# PWR.net
KiCad netlist of a schematic drawn in Altium Designer
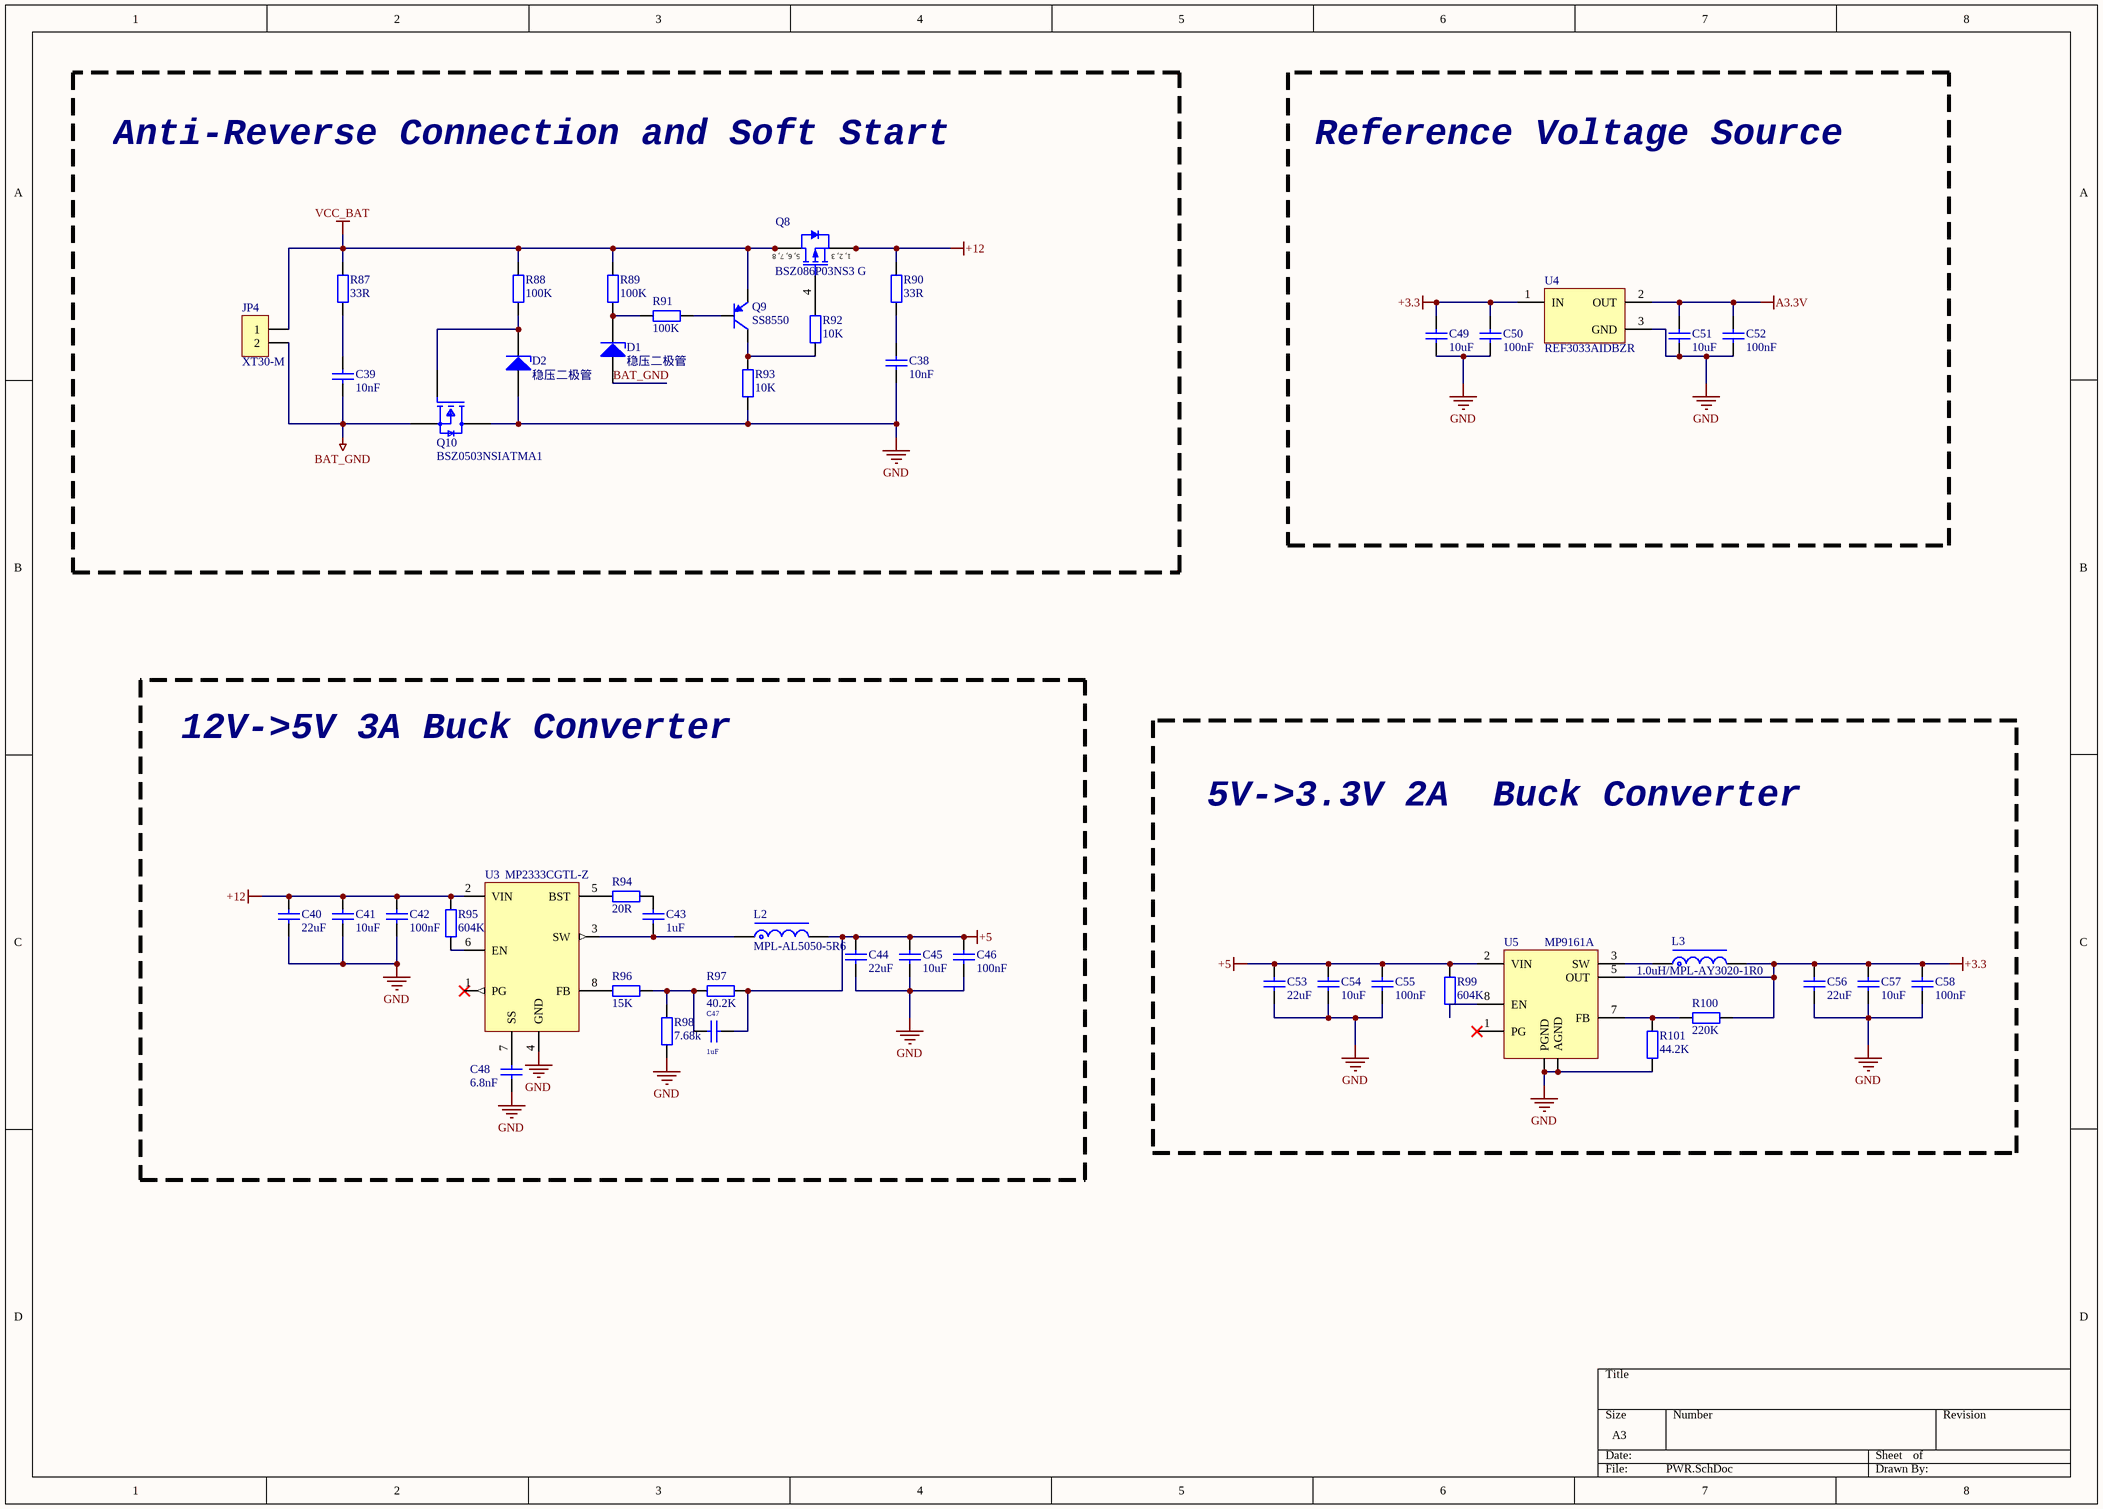
[diagram p0: PWR.SchDoc]

(export (version "E")
  (design (tool "Eeschema 10.0.6"))
  (components
    (comp (ref "C38")
      (value "10nF")
      (footprint "C0402_M")
      (description "贴片电容/MLCC电容")
      (libsource (lib "0.1 - 电阻-电容-电感-保险丝-晶振-晶体-磁珠-电位器-法拉电容-馈通电容") (part "C"))
    )
    (comp (ref "C39")
      (value "10nF")
      (footprint "C0402_M")
      (description "贴片电容/MLCC电容")
      (libsource (lib "0.1 - 电阻-电容-电感-保险丝-晶振-晶体-磁珠-电位器-法拉电容-馈通电容") (part "C"))
    )
    (comp (ref "C40")
      (value "22uF")
      (footprint "C0402_M")
      (description "贴片电容/MLCC电容")
      (libsource (lib "0.1 - 电阻-电容-电感-保险丝-晶振-晶体-磁珠-电位器-法拉电容-馈通电容") (part "C"))
    )
    (comp (ref "C41")
      (value "10uF")
      (footprint "C0402_M")
      (description "贴片电容/MLCC电容")
      (libsource (lib "0.1 - 电阻-电容-电感-保险丝-晶振-晶体-磁珠-电位器-法拉电容-馈通电容") (part "C"))
    )
    (comp (ref "C42")
      (value "100nF")
      (footprint "C0402_M")
      (description "贴片电容/MLCC电容")
      (libsource (lib "0.1 - 电阻-电容-电感-保险丝-晶振-晶体-磁珠-电位器-法拉电容-馈通电容") (part "C"))
    )
    (comp (ref "C43")
      (value "1uF")
      (footprint "C0402_M")
      (description "贴片电容/MLCC电容")
      (libsource (lib "0.1 - 电阻-电容-电感-保险丝-晶振-晶体-磁珠-电位器-法拉电容-馈通电容") (part "C"))
    )
    (comp (ref "C44")
      (value "22uF")
      (footprint "C0402_M")
      (description "贴片电容/MLCC电容")
      (libsource (lib "0.1 - 电阻-电容-电感-保险丝-晶振-晶体-磁珠-电位器-法拉电容-馈通电容") (part "C"))
    )
    (comp (ref "C45")
      (value "10uF")
      (footprint "C0402_M")
      (description "贴片电容/MLCC电容")
      (libsource (lib "0.1 - 电阻-电容-电感-保险丝-晶振-晶体-磁珠-电位器-法拉电容-馈通电容") (part "C"))
    )
    (comp (ref "C46")
      (value "100nF")
      (footprint "C0402_M")
      (description "贴片电容/MLCC电容")
      (libsource (lib "0.1 - 电阻-电容-电感-保险丝-晶振-晶体-磁珠-电位器-法拉电容-馈通电容") (part "C"))
    )
    (comp (ref "C47")
      (value "1uF")
      (footprint "C0402_M")
      (description "贴片电容/MLCC电容")
      (libsource (lib "0.1 - 电阻-电容-电感-保险丝-晶振-晶体-磁珠-电位器-法拉电容-馈通电容") (part "C"))
    )
    (comp (ref "C48")
      (value "6.8nF")
      (footprint "C0402_M")
      (description "贴片电容/MLCC电容")
      (libsource (lib "0.1 - 电阻-电容-电感-保险丝-晶振-晶体-磁珠-电位器-法拉电容-馈通电容") (part "C"))
    )
    (comp (ref "C49")
      (value "10uF")
      (footprint "C0402_M")
      (description "贴片电容/MLCC电容")
      (libsource (lib "0.1 - 电阻-电容-电感-保险丝-晶振-晶体-磁珠-电位器-法拉电容-馈通电容") (part "C"))
    )
    (comp (ref "C50")
      (value "100nF")
      (footprint "C0402_M")
      (description "贴片电容/MLCC电容")
      (libsource (lib "0.1 - 电阻-电容-电感-保险丝-晶振-晶体-磁珠-电位器-法拉电容-馈通电容") (part "C"))
    )
    (comp (ref "C51")
      (value "10uF")
      (footprint "C0402_M")
      (description "贴片电容/MLCC电容")
      (libsource (lib "0.1 - 电阻-电容-电感-保险丝-晶振-晶体-磁珠-电位器-法拉电容-馈通电容") (part "C"))
    )
    (comp (ref "C52")
      (value "100nF")
      (footprint "C0402_M")
      (description "贴片电容/MLCC电容")
      (libsource (lib "0.1 - 电阻-电容-电感-保险丝-晶振-晶体-磁珠-电位器-法拉电容-馈通电容") (part "C"))
    )
    (comp (ref "C53")
      (value "22uF")
      (footprint "C0402_M")
      (description "贴片电容/MLCC电容")
      (libsource (lib "0.1 - 电阻-电容-电感-保险丝-晶振-晶体-磁珠-电位器-法拉电容-馈通电容") (part "C"))
    )
    (comp (ref "C54")
      (value "10uF")
      (footprint "C0402_M")
      (description "贴片电容/MLCC电容")
      (libsource (lib "0.1 - 电阻-电容-电感-保险丝-晶振-晶体-磁珠-电位器-法拉电容-馈通电容") (part "C"))
    )
    (comp (ref "C55")
      (value "100nF")
      (footprint "C0402_M")
      (description "贴片电容/MLCC电容")
      (libsource (lib "0.1 - 电阻-电容-电感-保险丝-晶振-晶体-磁珠-电位器-法拉电容-馈通电容") (part "C"))
    )
    (comp (ref "C56")
      (value "22uF")
      (footprint "C0402_M")
      (description "贴片电容/MLCC电容")
      (libsource (lib "0.1 - 电阻-电容-电感-保险丝-晶振-晶体-磁珠-电位器-法拉电容-馈通电容") (part "C"))
    )
    (comp (ref "C57")
      (value "10uF")
      (footprint "C0402_M")
      (description "贴片电容/MLCC电容")
      (libsource (lib "0.1 - 电阻-电容-电感-保险丝-晶振-晶体-磁珠-电位器-法拉电容-馈通电容") (part "C"))
    )
    (comp (ref "C58")
      (value "100nF")
      (footprint "C0402_M")
      (description "贴片电容/MLCC电容")
      (libsource (lib "0.1 - 电阻-电容-电感-保险丝-晶振-晶体-磁珠-电位器-法拉电容-馈通电容") (part "C"))
    )
    (comp (ref "D1")
      (value "稳压二极管")
      (footprint "SOD-523")
      (description "Zener Diode")
      (libsource (lib "0.2 - 二极管-TVS-ESD-整流桥-放电管") (part "稳压二极管"))
    )
    (comp (ref "D2")
      (value "稳压二极管")
      (footprint "SOD-523")
      (description "Zener Diode")
      (libsource (lib "0.2 - 二极管-TVS-ESD-整流桥-放电管") (part "稳压二极管"))
    )
    (comp (ref "JP4")
      (value "XT30-M")
      (footprint "XT30PB-M")
      (description "XT30公头")
      (libsource (lib "0.6 - 电源_音频_USB Type-C_HDMI_XT60_5557_D-SUB_RJ45_SD-TF_SIM插座") (part "XT30-M"))
    )
    (comp (ref "L2")
      (value "MPL-AL5050-5R6")
      (footprint "MPL-AL5050")
      (description "一体成型电感")
      (libsource (lib "0.1 - 电阻-电容-电感-保险丝-晶振-晶体-磁珠-电位器-法拉电容-馈通电容") (part "L-Molding Choke"))
    )
    (comp (ref "L3")
      (value "1.0uH/MPL-AY3020-1R0")
      (footprint "MPL-AY3020")
      (description "一体成型电感")
      (libsource (lib "0.1 - 电阻-电容-电感-保险丝-晶振-晶体-磁珠-电位器-法拉电容-馈通电容") (part "L-Molding Choke"))
    )
    (comp (ref "Q8")
      (value "BSZ086P03NS3 G")
      (footprint "INF-PG-TSDSON-8-1_V")
      (fields (field (name "MANUFACTURER") "Infineon"))
      (libsource (lib "Altium Content Vault") (part "INF-PEMOS-SSSGDDDD-8"))
    )
    (comp (ref "Q9")
      (value "SS8550")
      (footprint "SOT23-3N")
      (description "高频放大-PNP型")
      (libsource (lib "0.4 - 三极管-场效应管-可控硅") (part "8550-SMD"))
    )
    (comp (ref "Q10")
      (value "BSZ0503NSIATMA1")
      (footprint "FP-PG-TSDSON-8-MFG")
      (description "BSZ0503NSI series 30V 40A 3.4 mOhm N-Ch S3O8 OptiMOS 5")
      (libsource (lib "海南大学MECHA战队") (part "3085234d4498bcd04bc7e5400bb7c96"))
    )
    (comp (ref "R87")
      (value "33R")
      (footprint "R0402_L")
      (description "贴片电阻0")
      (libsource (lib "海南大学MECHA战队") (part "R-High Precision"))
    )
    (comp (ref "R88")
      (value "100K")
      (footprint "R0402_L")
      (description "贴片电阻0")
      (libsource (lib "海南大学MECHA战队") (part "R-High Precision"))
    )
    (comp (ref "R89")
      (value "100K")
      (footprint "R0402_L")
      (description "贴片电阻0")
      (libsource (lib "海南大学MECHA战队") (part "R-High Precision"))
    )
    (comp (ref "R90")
      (value "33R")
      (footprint "R0402_L")
      (description "贴片电阻0")
      (libsource (lib "海南大学MECHA战队") (part "R-High Precision"))
    )
    (comp (ref "R91")
      (value "100K")
      (footprint "R0402_L")
      (description "贴片电阻0")
      (libsource (lib "海南大学MECHA战队") (part "R-High Precision"))
    )
    (comp (ref "R92")
      (value "10K")
      (footprint "R0402_L")
      (description "贴片电阻0")
      (libsource (lib "海南大学MECHA战队") (part "R-High Precision"))
    )
    (comp (ref "R93")
      (value "10K")
      (footprint "R0402_L")
      (description "贴片电阻0")
      (libsource (lib "海南大学MECHA战队") (part "R-High Precision"))
    )
    (comp (ref "R94")
      (value "20R")
      (footprint "R0402_L")
      (description "贴片电阻0")
      (libsource (lib "海南大学MECHA战队") (part "R-High Precision"))
    )
    (comp (ref "R95")
      (value "604K")
      (footprint "R0402_L")
      (description "贴片电阻0")
      (libsource (lib "海南大学MECHA战队") (part "R-High Precision"))
    )
    (comp (ref "R96")
      (value "15K")
      (footprint "R0402_L")
      (description "贴片电阻0")
      (libsource (lib "海南大学MECHA战队") (part "R-High Precision"))
    )
    (comp (ref "R97")
      (value "40.2K")
      (footprint "R0402_L")
      (description "贴片电阻0")
      (libsource (lib "海南大学MECHA战队") (part "R-High Precision"))
    )
    (comp (ref "R98")
      (value "7.68k")
      (footprint "R0402_L")
      (description "贴片电阻0")
      (libsource (lib "海南大学MECHA战队") (part "R-High Precision"))
    )
    (comp (ref "R99")
      (value "604K")
      (footprint "R0402_L")
      (description "贴片电阻0")
      (libsource (lib "海南大学MECHA战队") (part "R-High Precision"))
    )
    (comp (ref "R100")
      (value "220K")
      (footprint "R0402_L")
      (description "贴片电阻0")
      (libsource (lib "海南大学MECHA战队") (part "R-High Precision"))
    )
    (comp (ref "R101")
      (value "44.2K")
      (footprint "R0402_L")
      (description "贴片电阻0")
      (libsource (lib "海南大学MECHA战队") (part "R-High Precision"))
    )
    (comp (ref "U3")
      (value "MP2333CGTL-Z")
      (footprint "SOT583_MP2333C_MNP")
      (description "Switching Voltage Regulators 3A, 18V, 650kHz, Force CCM, Synchronous Step-Down C")
      (libsource (lib "海南大学MECHA战队") (part "MP2333CGTL-Z"))
    )
    (comp (ref "U4")
      (value "REF3033AIDBZR")
      (footprint "DBZ0003A_N")
      (fields (field (name "MANUFACTURER") "Texas Instruments"))
      (libsource (lib "Altium Content Vault") (part "TI-REF3033DBZ3"))
    )
    (comp (ref "U5") (value "MP9161A") (footprint "SOT23-8") (libsource (lib "海南大学MECHA战队") (part "MP9161A")))
  )
  (nets
    (net (code "1") (name "+3.3") (class "Default")
      (node (ref "C49") (pin "2") (pinfunction "2_2") (pintype "passive"))
      (node (ref "C50") (pin "2") (pinfunction "2_2") (pintype "passive"))
      (node (ref "C56") (pin "2") (pinfunction "2_2") (pintype "passive"))
      (node (ref "C57") (pin "2") (pinfunction "2_2") (pintype "passive"))
      (node (ref "C58") (pin "2") (pinfunction "2_2") (pintype "passive"))
      (node (ref "L3") (pin "2") (pinfunction "2_2") (pintype "passive"))
      (node (ref "R100") (pin "2") (pinfunction "2_2") (pintype "passive"))
      (node (ref "U4") (pin "1") (pinfunction "IN_1") (pintype "power_in"))
      (node (ref "U5") (pin "5") (pinfunction "OUT_5") (pintype "passive"))
    )
    (net (code "2") (name "+5") (class "Default")
      (node (ref "C44") (pin "2") (pinfunction "2_2") (pintype "passive"))
      (node (ref "C45") (pin "2") (pinfunction "2_2") (pintype "passive"))
      (node (ref "C46") (pin "2") (pinfunction "2_2") (pintype "passive"))
      (node (ref "C47") (pin "1") (pinfunction "1_1") (pintype "passive"))
      (node (ref "C53") (pin "2") (pinfunction "2_2") (pintype "passive"))
      (node (ref "C54") (pin "2") (pinfunction "2_2") (pintype "passive"))
      (node (ref "C55") (pin "2") (pinfunction "2_2") (pintype "passive"))
      (node (ref "L2") (pin "2") (pinfunction "2_2") (pintype "passive"))
      (node (ref "R97") (pin "2") (pinfunction "2_2") (pintype "passive"))
      (node (ref "R99") (pin "2") (pinfunction "2_2") (pintype "passive"))
      (node (ref "U5") (pin "2") (pinfunction "VIN_2") (pintype "passive"))
    )
    (net (code "3") (name "+12") (class "Default")
      (node (ref "C40") (pin "2") (pinfunction "2_2") (pintype "passive"))
      (node (ref "C41") (pin "2") (pinfunction "2_2") (pintype "passive"))
      (node (ref "C42") (pin "2") (pinfunction "2_2") (pintype "passive"))
      (node (ref "Q8") (pin "1") (pinfunction "SOURCE_1") (pintype "passive"))
      (node (ref "Q8") (pin "2") (pinfunction "SOURCE_2") (pintype "passive"))
      (node (ref "Q8") (pin "3") (pinfunction "SOURCE_3") (pintype "passive"))
      (node (ref "R90") (pin "2") (pinfunction "2_2") (pintype "passive"))
      (node (ref "R95") (pin "2") (pinfunction "2_2") (pintype "passive"))
      (node (ref "U3") (pin "2") (pinfunction "VIN_2") (pintype "power_in"))
    )
    (net (code "4") (name "A3.3V") (class "Default")
      (node (ref "C51") (pin "2") (pinfunction "2_2") (pintype "passive"))
      (node (ref "C52") (pin "2") (pinfunction "2_2") (pintype "passive"))
      (node (ref "U4") (pin "2") (pinfunction "OUT_2") (pintype "power_in"))
    )
    (net (code "5") (name "BAT_GND") (class "Default")
      (node (ref "C39") (pin "1") (pinfunction "1_1") (pintype "passive"))
      (node (ref "D1") (pin "1") (pinfunction "A_1") (pintype "passive"))
      (node (ref "JP4") (pin "2") (pinfunction "2_2") (pintype "passive"))
      (node (ref "Q10") (pin "1-2-3") (pinfunction "S_1-2-3") (pintype "passive"))
    )
    (net (code "6") (name "GND") (class "Default")
      (node (ref "C38") (pin "1") (pinfunction "1_1") (pintype "passive"))
      (node (ref "C40") (pin "1") (pinfunction "1_1") (pintype "passive"))
      (node (ref "C41") (pin "1") (pinfunction "1_1") (pintype "passive"))
      (node (ref "C42") (pin "1") (pinfunction "1_1") (pintype "passive"))
      (node (ref "C44") (pin "1") (pinfunction "1_1") (pintype "passive"))
      (node (ref "C45") (pin "1") (pinfunction "1_1") (pintype "passive"))
      (node (ref "C46") (pin "1") (pinfunction "1_1") (pintype "passive"))
      (node (ref "C48") (pin "2") (pinfunction "2_2") (pintype "passive"))
      (node (ref "C49") (pin "1") (pinfunction "1_1") (pintype "passive"))
      (node (ref "C50") (pin "1") (pinfunction "1_1") (pintype "passive"))
      (node (ref "C51") (pin "1") (pinfunction "1_1") (pintype "passive"))
      (node (ref "C52") (pin "1") (pinfunction "1_1") (pintype "passive"))
      (node (ref "C53") (pin "1") (pinfunction "1_1") (pintype "passive"))
      (node (ref "C54") (pin "1") (pinfunction "1_1") (pintype "passive"))
      (node (ref "C55") (pin "1") (pinfunction "1_1") (pintype "passive"))
      (node (ref "C56") (pin "1") (pinfunction "1_1") (pintype "passive"))
      (node (ref "C57") (pin "1") (pinfunction "1_1") (pintype "passive"))
      (node (ref "C58") (pin "1") (pinfunction "1_1") (pintype "passive"))
      (node (ref "D2") (pin "1") (pinfunction "A_1") (pintype "passive"))
      (node (ref "Q10") (pin "5-6-7-8") (pinfunction "D_5-6-7-8") (pintype "passive"))
      (node (ref "R101") (pin "2") (pinfunction "2_2") (pintype "passive"))
      (node (ref "R93") (pin "2") (pinfunction "2_2") (pintype "passive"))
      (node (ref "R98") (pin "2") (pinfunction "2_2") (pintype "passive"))
      (node (ref "U3") (pin "4") (pinfunction "GND_4") (pintype "power_in"))
      (node (ref "U4") (pin "3") (pinfunction "GND_3") (pintype "power_in"))
      (node (ref "U5") (pin "4") (pinfunction "PGND_4") (pintype "passive"))
      (node (ref "U5") (pin "6") (pinfunction "AGND_6") (pintype "passive"))
    )
    (net (code "7") (name "Net-(C38-Pad2)") (class "Default")
      (node (ref "C38") (pin "2") (pinfunction "2_2") (pintype "passive"))
      (node (ref "R90") (pin "1") (pinfunction "1_1") (pintype "passive"))
    )
    (net (code "8") (name "Net-(C39-Pad2)") (class "Default")
      (node (ref "C39") (pin "2") (pinfunction "2_2") (pintype "passive"))
      (node (ref "R87") (pin "1") (pinfunction "1_1") (pintype "passive"))
    )
    (net (code "9") (name "Net-(C43-Pad2)") (class "Default")
      (node (ref "C43") (pin "2") (pinfunction "2_2") (pintype "passive"))
      (node (ref "R94") (pin "1") (pinfunction "1_1") (pintype "passive"))
    )
    (net (code "10") (name "Net-(C47-Pad2)") (class "Default")
      (node (ref "C47") (pin "2") (pinfunction "2_2") (pintype "passive"))
      (node (ref "R96") (pin "1") (pinfunction "1_1") (pintype "passive"))
      (node (ref "R97") (pin "1") (pinfunction "1_1") (pintype "passive"))
      (node (ref "R98") (pin "1") (pinfunction "1_1") (pintype "passive"))
    )
    (net (code "11") (name "Net-(D1-K)") (class "Default")
      (node (ref "D1") (pin "2") (pinfunction "K_2") (pintype "passive"))
      (node (ref "R89") (pin "1") (pinfunction "1_1") (pintype "passive"))
      (node (ref "R91") (pin "2") (pinfunction "2_2") (pintype "passive"))
    )
    (net (code "12") (name "Net-(D2-K)") (class "Default")
      (node (ref "D2") (pin "2") (pinfunction "K_2") (pintype "passive"))
      (node (ref "Q10") (pin "4") (pinfunction "G_4") (pintype "passive"))
      (node (ref "R88") (pin "1") (pinfunction "1_1") (pintype "passive"))
    )
    (net (code "13") (name "Net-(Q8-GATE)") (class "Default")
      (node (ref "Q8") (pin "4") (pinfunction "GATE_4") (pintype "passive"))
      (node (ref "R92") (pin "1") (pinfunction "1_1") (pintype "passive"))
    )
    (net (code "14") (name "Net-(Q9-B)") (class "Default")
      (node (ref "Q9") (pin "1") (pinfunction "B_1") (pintype "passive"))
      (node (ref "R91") (pin "1") (pinfunction "1_1") (pintype "passive"))
    )
    (net (code "15") (name "Net-(Q9-C)") (class "Default")
      (node (ref "Q9") (pin "3") (pinfunction "C_3") (pintype "passive"))
      (node (ref "R92") (pin "2") (pinfunction "2_2") (pintype "passive"))
      (node (ref "R93") (pin "1") (pinfunction "1_1") (pintype "passive"))
    )
    (net (code "16") (name "Net-(U3-BST)") (class "Default")
      (node (ref "R94") (pin "2") (pinfunction "2_2") (pintype "passive"))
      (node (ref "U3") (pin "5") (pinfunction "BST_5") (pintype "passive"))
    )
    (net (code "17") (name "Net-(U3-EN)") (class "Default")
      (node (ref "R95") (pin "1") (pinfunction "1_1") (pintype "passive"))
      (node (ref "U3") (pin "6") (pinfunction "EN_6") (pintype "passive"))
    )
    (net (code "18") (name "Net-(U3-FB)") (class "Default")
      (node (ref "R96") (pin "2") (pinfunction "2_2") (pintype "passive"))
      (node (ref "U3") (pin "8") (pinfunction "FB_8") (pintype "passive"))
    )
    (net (code "19") (name "Net-(U3-SS)") (class "Default")
      (node (ref "C48") (pin "1") (pinfunction "1_1") (pintype "passive"))
      (node (ref "U3") (pin "7") (pinfunction "SS_7") (pintype "passive"))
    )
    (net (code "20") (name "Net-(U3-SW)") (class "Default")
      (node (ref "C43") (pin "1") (pinfunction "1_1") (pintype "passive"))
      (node (ref "L2") (pin "1") (pinfunction "1_1") (pintype "passive"))
      (node (ref "U3") (pin "3") (pinfunction "SW_3") (pintype "output"))
    )
    (net (code "21") (name "Net-(U5-EN)") (class "Default")
      (node (ref "R99") (pin "1") (pinfunction "1_1") (pintype "passive"))
      (node (ref "U5") (pin "8") (pinfunction "EN_8") (pintype "passive"))
    )
    (net (code "22") (name "Net-(U5-FB)") (class "Default")
      (node (ref "R100") (pin "1") (pinfunction "1_1") (pintype "passive"))
      (node (ref "R101") (pin "1") (pinfunction "1_1") (pintype "passive"))
      (node (ref "U5") (pin "7") (pinfunction "FB_7") (pintype "passive"))
    )
    (net (code "23") (name "Net-(U5-SW)") (class "Default")
      (node (ref "L3") (pin "1") (pinfunction "1_1") (pintype "passive"))
      (node (ref "U5") (pin "3") (pinfunction "SW_3") (pintype "passive"))
    )
    (net (code "24") (name "VCC_BAT") (class "Default")
      (node (ref "JP4") (pin "1") (pinfunction "1_1") (pintype "passive"))
      (node (ref "Q8") (pin "5") (pinfunction "DRAIN_5") (pintype "passive"))
      (node (ref "Q8") (pin "6") (pinfunction "DRAIN_6") (pintype "passive"))
      (node (ref "Q8") (pin "7") (pinfunction "DRAIN_7") (pintype "passive"))
      (node (ref "Q8") (pin "8") (pinfunction "DRAIN_8") (pintype "passive"))
      (node (ref "Q9") (pin "2") (pinfunction "E_2") (pintype "passive"))
      (node (ref "R87") (pin "2") (pinfunction "2_2") (pintype "passive"))
      (node (ref "R88") (pin "2") (pinfunction "2_2") (pintype "passive"))
      (node (ref "R89") (pin "2") (pinfunction "2_2") (pintype "passive"))
    )
    (net (code "25") (name "unconnected-(U3-PG-Pad1)") (class "Default")
      (node (ref "U3") (pin "1") (pinfunction "PG_1") (pintype "output+no_connect"))
    )
    (net (code "26") (name "unconnected-(U5-PG-Pad1)") (class "Default")
      (node (ref "U5") (pin "1") (pinfunction "PG_1") (pintype "passive+no_connect"))
    )
  )
)
